# MCU.net
KiCad netlist of a schematic drawn in EAGLE
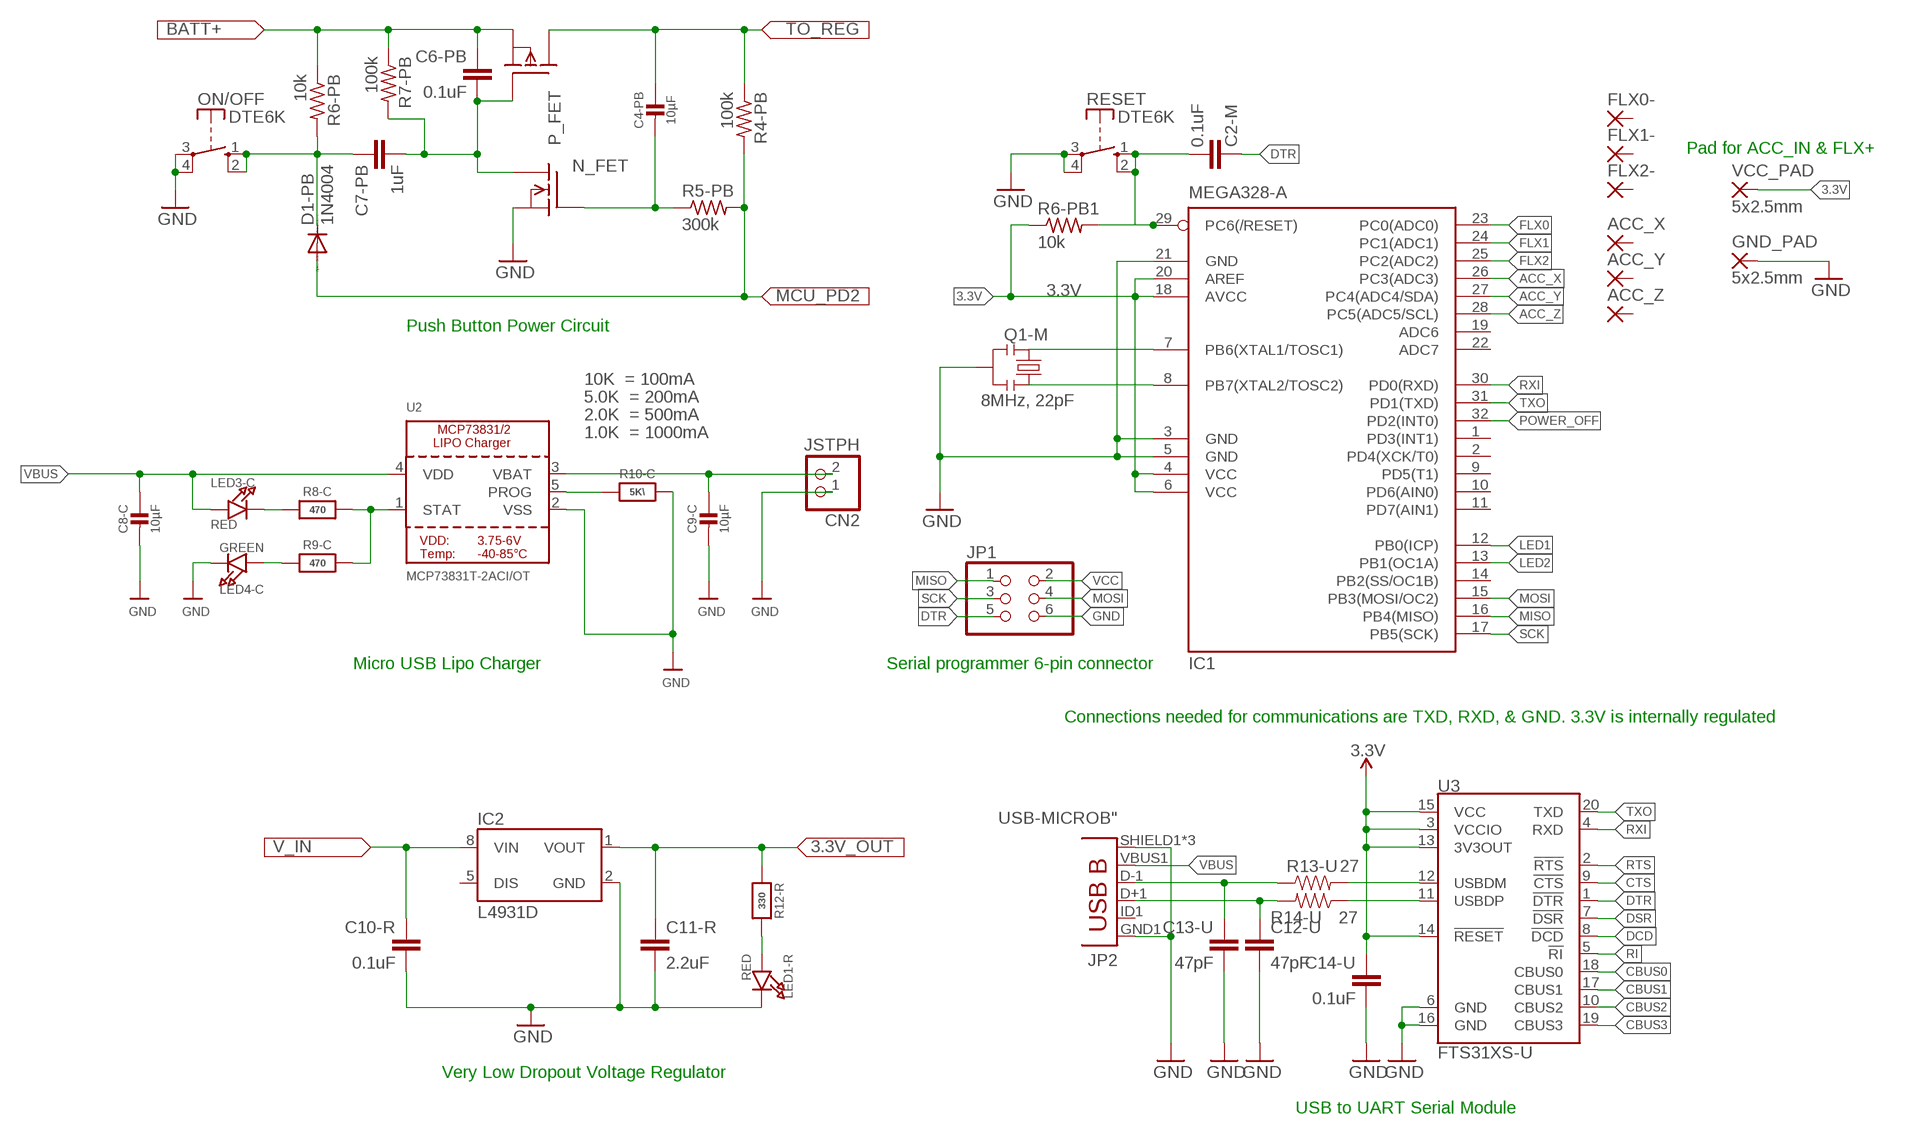
[diagram p0: schematic, sheet 1]

(export (version "E")
  (design (tool "Eeschema 10.0.6"))
  (components
    (comp (ref "ACC_X")
      (value "1,6/0,8")
      (footprint "eagle-import:1,6_0,8")
      (libsource (lib "eagle-import") (part "1,6/0,8"))
    )
    (comp (ref "ACC_Y")
      (value "1,6/0,8")
      (footprint "eagle-import:1,6_0,8")
      (libsource (lib "eagle-import") (part "1,6/0,8"))
    )
    (comp (ref "ACC_Z")
      (value "1,6/0,8")
      (footprint "eagle-import:1,6_0,8")
      (libsource (lib "eagle-import") (part "1,6/0,8"))
    )
    (comp (ref "C2-M")
      (value "0.1uF")
      (footprint "eagle-import:0603-CAP")
      (libsource (lib "eagle-import") (part "CAP0603-CAP"))
    )
    (comp (ref "C4-PB")
      (value "10µF")
      (footprint "eagle-import:0805-NO")
      (libsource (lib "eagle-import") (part "CAP_CERAMIC0805-NOOUTLINE"))
    )
    (comp (ref "C6-PB")
      (value "0.1uF")
      (footprint "eagle-import:0603-CAP")
      (libsource (lib "eagle-import") (part "0.1UF-25V(+80/-20%)(0603)"))
    )
    (comp (ref "C7-PB")
      (value "1uF")
      (footprint "eagle-import:0603-CAP")
      (libsource (lib "eagle-import") (part "0.1UF-25V(+80/-20%)(0603)"))
    )
    (comp (ref "C8-C")
      (value "10µF")
      (footprint "eagle-import:0805-NO")
      (libsource (lib "eagle-import") (part "CAP_CERAMIC0805-NOOUTLINE"))
    )
    (comp (ref "C9-C")
      (value "10µF")
      (footprint "eagle-import:0805-NO")
      (libsource (lib "eagle-import") (part "CAP_CERAMIC0805-NOOUTLINE"))
    )
    (comp (ref "C10-R")
      (value "0.1uF")
      (footprint "eagle-import:0603-CAP")
      (libsource (lib "eagle-import") (part "0.1UF-25V(+80/-20%)(0603)"))
    )
    (comp (ref "C11-R")
      (value "2.2uF")
      (footprint "eagle-import:0603-CAP")
      (libsource (lib "eagle-import") (part "0.1UF-25V(+80/-20%)(0603)"))
    )
    (comp (ref "C12-U")
      (value "47pF")
      (footprint "eagle-import:0603-CAP")
      (libsource (lib "eagle-import") (part "47PF-50V-5%(0603)"))
    )
    (comp (ref "C13-U")
      (value "47pF")
      (footprint "eagle-import:0603-CAP")
      (libsource (lib "eagle-import") (part "47PF-50V-5%(0603)"))
    )
    (comp (ref "C14-U")
      (value "0.1uF")
      (footprint "eagle-import:0603-CAP")
      (libsource (lib "eagle-import") (part "0.1UF-25V(+80/-20%)(0603)"))
    )
    (comp (ref "CN2")
      (value "JSTPH")
      (footprint "eagle-import:JSTPH2")
      (libsource (lib "eagle-import") (part "JST_2PIN"))
    )
    (comp (ref "D1-PB")
      (value "1N4004")
      (footprint "eagle-import:DO41-10")
      (libsource (lib "eagle-import") (part "1N4004"))
    )
    (comp (ref "FLX0-")
      (value "1,6/0,8")
      (footprint "eagle-import:1,6_0,8")
      (libsource (lib "eagle-import") (part "1,6/0,8"))
    )
    (comp (ref "FLX1-")
      (value "1,6/0,8")
      (footprint "eagle-import:1,6_0,8")
      (libsource (lib "eagle-import") (part "1,6/0,8"))
    )
    (comp (ref "FLX2-")
      (value "1,6/0,8")
      (footprint "eagle-import:1,6_0,8")
      (libsource (lib "eagle-import") (part "1,6/0,8"))
    )
    (comp (ref "GND_PAD")
      (value "5x2.5mm")
      (footprint "eagle-import:5-2,5")
      (libsource (lib "eagle-import") (part "WIREPADSMD5-2,5"))
    )
    (comp (ref "IC1")
      (value "MEGA328-A")
      (footprint "eagle-import:TQFP32-08")
      (fields (field (name "MPN") "ATMEGA8-16AU"))
      (libsource (lib "eagle-import") (part "MEGA8-AI"))
    )
    (comp (ref "IC2")
      (value "L4931D")
      (footprint "eagle-import:SO08")
      (libsource (lib "eagle-import") (part "L4931D"))
    )
    (comp (ref "JP1")
      (value "PINHD-2X3")
      (footprint "eagle-import:2X03")
      (libsource (lib "eagle-import") (part "PINHD-2X3"))
    )
    (comp (ref "JP2")
      (value "USB-MICROB\"")
      (footprint "eagle-import:USB-B-MICRO-SMD_V03")
      (libsource (lib "eagle-import") (part "USB-MICROB{dblquote}"))
    )
    (comp (ref "LED1-R")
      (value "RED")
      (footprint "eagle-import:CHIPLED_0805_NOOUTLINE")
      (libsource (lib "eagle-import") (part "LED0805_NOOUTLINE"))
    )
    (comp (ref "LED3-C")
      (value "RED")
      (footprint "eagle-import:CHIPLED_0805_NOOUTLINE")
      (libsource (lib "eagle-import") (part "LED0805_NOOUTLINE"))
    )
    (comp (ref "LED4-C")
      (value "GREEN")
      (footprint "eagle-import:CHIPLED_0805_NOOUTLINE")
      (libsource (lib "eagle-import") (part "LED0805_NOOUTLINE"))
    )
    (comp (ref "N_FET")
      (value "BSS101")
      (footprint "eagle-import:TO92")
      (libsource (lib "eagle-import") (part "BSS101"))
    )
    (comp (ref "ON/OFF")
      (value "DTE6K")
      (footprint "eagle-import:DTE6K")
      (libsource (lib "eagle-import") (part "DTE6K"))
    )
    (comp (ref "P_FET")
      (value "BSS92")
      (footprint "eagle-import:TO92")
      (libsource (lib "eagle-import") (part "BSS92"))
    )
    (comp (ref "Q1-M")
      (value "8MHz, 22pF")
      (footprint "eagle-import:RESONATOR-SMD-1_1")
      (libsource (lib "eagle-import") (part "RESONATOR1{colon}1"))
    )
    (comp (ref "R4-PB")
      (value "100k")
      (footprint "eagle-import:R0805")
      (libsource (lib "eagle-import") (part "R-US_R0805"))
    )
    (comp (ref "R5-PB")
      (value "300k")
      (footprint "eagle-import:R0805")
      (libsource (lib "eagle-import") (part "R-US_R0805"))
    )
    (comp (ref "R6-PB")
      (value "10k")
      (footprint "eagle-import:R0805")
      (libsource (lib "eagle-import") (part "R-US_R0805"))
    )
    (comp (ref "R6-PB1")
      (value "10k")
      (footprint "eagle-import:R0805")
      (libsource (lib "eagle-import") (part "R-US_R0805"))
    )
    (comp (ref "R7-PB")
      (value "100k")
      (footprint "eagle-import:R0805")
      (libsource (lib "eagle-import") (part "R-US_R0805"))
    )
    (comp (ref "R8-C")
      (value "470")
      (footprint "eagle-import:0805-NO")
      (libsource (lib "eagle-import") (part "RESISTOR0805_NOOUTLINE"))
    )
    (comp (ref "R9-C")
      (value "470")
      (footprint "eagle-import:0805-NO")
      (libsource (lib "eagle-import") (part "RESISTOR0805_NOOUTLINE"))
    )
    (comp (ref "R10-C")
      (value "5K\\")
      (footprint "eagle-import:0805-NO")
      (libsource (lib "eagle-import") (part "RESISTOR0805_NOOUTLINE"))
    )
    (comp (ref "R12-R")
      (value "330")
      (footprint "eagle-import:0805-NO")
      (libsource (lib "eagle-import") (part "RESISTOR0805_NOOUTLINE"))
    )
    (comp (ref "R13-U")
      (value "27")
      (footprint "eagle-import:0603-RES")
      (libsource (lib "eagle-import") (part "27OHM1/10W1%(0603)0603-RES"))
    )
    (comp (ref "R14-U")
      (value "27")
      (footprint "eagle-import:0603-RES")
      (libsource (lib "eagle-import") (part "27OHM1/10W1%(0603)0603-RES"))
    )
    (comp (ref "RESET")
      (value "DTE6K")
      (footprint "eagle-import:DTE6K")
      (libsource (lib "eagle-import") (part "DTE6K"))
    )
    (comp (ref "U2")
      (value "MCP73831T-2ACI/OT")
      (footprint "eagle-import:SOT23-5")
      (libsource (lib "eagle-import") (part "MCP73831/2"))
    )
    (comp (ref "U3")
      (value "FTS31XS-U")
      (footprint "eagle-import:SSOP20_L")
      (libsource (lib "eagle-import") (part "FT231XS"))
    )
    (comp (ref "VCC_PAD")
      (value "5x2.5mm")
      (footprint "eagle-import:5-2,5")
      (libsource (lib "eagle-import") (part "WIREPADSMD5-2,5"))
    )
  )
  (nets
    (net (code "1") (name "/VBAT") (class "Default")
      (node (ref "C6-PB") (pin "1") (pinfunction "1_1") (pintype "passive"))
      (node (ref "C9-C") (pin "1") (pinfunction "1_1") (pintype "passive"))
      (node (ref "CN2") (pin "2") (pinfunction "2_2") (pintype "passive"))
      (node (ref "P_FET") (pin "3") (pinfunction "S_3") (pintype "passive"))
      (node (ref "R6-PB") (pin "1") (pinfunction "1_1") (pintype "passive"))
      (node (ref "R7-PB") (pin "1") (pinfunction "1_1") (pintype "passive"))
      (node (ref "U2") (pin "3") (pinfunction "VBAT_3") (pintype "power_in"))
    )
    (net (code "2") (name "/V_IN") (class "Default")
      (node (ref "C10-R") (pin "1") (pinfunction "1_1") (pintype "passive"))
      (node (ref "C4-PB") (pin "1") (pinfunction "1_1") (pintype "passive"))
      (node (ref "IC2") (pin "8") (pinfunction "VIN_8") (pintype "power_in"))
      (node (ref "P_FET") (pin "2") (pinfunction "D_2") (pintype "passive"))
      (node (ref "R4-PB") (pin "1") (pinfunction "1_1") (pintype "passive"))
    )
    (net (code "3") (name "3.3V") (class "Default")
      (node (ref "C11-R") (pin "1") (pinfunction "1_1") (pintype "passive"))
      (node (ref "C14-U") (pin "1") (pinfunction "1_1") (pintype "passive"))
      (node (ref "IC1") (pin "18") (pinfunction "AVCC_18") (pintype "power_in"))
      (node (ref "IC1") (pin "20") (pinfunction "AREF_20") (pintype "passive"))
      (node (ref "IC1") (pin "4") (pinfunction "VCC_4") (pintype "power_in"))
      (node (ref "IC1") (pin "6") (pinfunction "VCC_6") (pintype "power_in"))
      (node (ref "IC2") (pin "1") (pinfunction "VOUT_1") (pintype "power_in"))
      (node (ref "R12-R") (pin "1") (pinfunction "1_1") (pintype "passive"))
      (node (ref "R6-PB1") (pin "1") (pinfunction "1_1") (pintype "passive"))
      (node (ref "U3") (pin "13") (pinfunction "3V3OUT_13") (pintype "bidirectional"))
      (node (ref "U3") (pin "14") (pinfunction "~{RESET}_14") (pintype "bidirectional"))
      (node (ref "U3") (pin "15") (pinfunction "VCC_15") (pintype "bidirectional"))
      (node (ref "U3") (pin "3") (pinfunction "VCCIO_3") (pintype "bidirectional"))
      (node (ref "VCC_PAD") (pin "1") (pinfunction "P_1") (pintype "passive"))
    )
    (net (code "4") (name "ACC_X") (class "Default")
      (node (ref "IC1") (pin "26") (pinfunction "PC3(ADC3)_26") (pintype "bidirectional"))
    )
    (net (code "5") (name "ACC_Y") (class "Default")
      (node (ref "IC1") (pin "27") (pinfunction "PC4(ADC4/SDA)_27") (pintype "bidirectional"))
    )
    (net (code "6") (name "ACC_Z") (class "Default")
      (node (ref "IC1") (pin "28") (pinfunction "PC5(ADC5/SCL)_28") (pintype "bidirectional"))
    )
    (net (code "7") (name "CBUS0") (class "Default")
      (node (ref "U3") (pin "18") (pinfunction "CBUS0_18") (pintype "bidirectional"))
    )
    (net (code "8") (name "CBUS1") (class "Default")
      (node (ref "U3") (pin "17") (pinfunction "CBUS1_17") (pintype "bidirectional"))
    )
    (net (code "9") (name "CBUS2") (class "Default")
      (node (ref "U3") (pin "10") (pinfunction "CBUS2_10") (pintype "bidirectional"))
    )
    (net (code "10") (name "CBUS3") (class "Default")
      (node (ref "U3") (pin "19") (pinfunction "CBUS3_19") (pintype "bidirectional"))
    )
    (net (code "11") (name "CTS") (class "Default")
      (node (ref "U3") (pin "9") (pinfunction "~{CTS}_9") (pintype "bidirectional"))
    )
    (net (code "12") (name "DCD") (class "Default")
      (node (ref "U3") (pin "8") (pinfunction "~{DCD}_8") (pintype "bidirectional"))
    )
    (net (code "13") (name "DSR") (class "Default")
      (node (ref "U3") (pin "7") (pinfunction "~{DSR}_7") (pintype "bidirectional"))
    )
    (net (code "14") (name "DTR") (class "Default")
      (node (ref "C2-M") (pin "2") (pinfunction "2_2") (pintype "passive"))
      (node (ref "JP1") (pin "5") (pinfunction "5_5") (pintype "passive"))
      (node (ref "U3") (pin "1") (pinfunction "~{DTR}_1") (pintype "bidirectional"))
    )
    (net (code "15") (name "FLX0") (class "Default")
      (node (ref "IC1") (pin "23") (pinfunction "PC0(ADC0)_23") (pintype "bidirectional"))
    )
    (net (code "16") (name "FLX1") (class "Default")
      (node (ref "IC1") (pin "24") (pinfunction "PC1(ADC1)_24") (pintype "bidirectional"))
    )
    (net (code "17") (name "FLX2") (class "Default")
      (node (ref "IC1") (pin "25") (pinfunction "PC2(ADC2)_25") (pintype "bidirectional"))
    )
    (net (code "18") (name "GND") (class "Default")
      (node (ref "C10-R") (pin "2") (pinfunction "2_2") (pintype "passive"))
      (node (ref "C11-R") (pin "2") (pinfunction "2_2") (pintype "passive"))
      (node (ref "C12-U") (pin "2") (pinfunction "2_2") (pintype "passive"))
      (node (ref "C13-U") (pin "2") (pinfunction "2_2") (pintype "passive"))
      (node (ref "C14-U") (pin "2") (pinfunction "2_2") (pintype "passive"))
      (node (ref "C8-C") (pin "2") (pinfunction "2_2") (pintype "passive"))
      (node (ref "C9-C") (pin "2") (pinfunction "2_2") (pintype "passive"))
      (node (ref "CN2") (pin "1") (pinfunction "1_1") (pintype "passive"))
      (node (ref "GND_PAD") (pin "1") (pinfunction "P_1") (pintype "passive"))
      (node (ref "IC1") (pin "21") (pinfunction "GND_21") (pintype "power_in"))
      (node (ref "IC1") (pin "3") (pinfunction "GND_3") (pintype "power_in"))
      (node (ref "IC1") (pin "5") (pinfunction "GND_5") (pintype "power_in"))
      (node (ref "IC2") (pin "2") (pinfunction "GND_2") (pintype "power_in"))
      (node (ref "JP1") (pin "6") (pinfunction "6_6") (pintype "passive"))
      (node (ref "JP2") (pin "GND1") (pinfunction "GND_GND1") (pintype "bidirectional"))
      (node (ref "JP2") (pin "SHIELD1") (pinfunction "SHIELD_SHIELD1") (pintype "bidirectional"))
      (node (ref "JP2") (pin "SHIELD2") (pinfunction "SHIELD_SHIELD2") (pintype "bidirectional"))
      (node (ref "JP2") (pin "SHIELD3") (pinfunction "SHIELD_SHIELD3") (pintype "bidirectional"))
      (node (ref "LED1-R") (pin "C") (pinfunction "C_C") (pintype "passive"))
      (node (ref "LED4-C") (pin "C") (pinfunction "C_C") (pintype "passive"))
      (node (ref "N_FET") (pin "1") (pinfunction "S_1") (pintype "passive"))
      (node (ref "ON/OFF") (pin "3") (pinfunction "P_3") (pintype "passive"))
      (node (ref "ON/OFF") (pin "4") (pinfunction "P_4") (pintype "passive"))
      (node (ref "Q1-M") (pin "2") (pinfunction "2_2") (pintype "passive"))
      (node (ref "R10-C") (pin "2") (pinfunction "2_2") (pintype "passive"))
      (node (ref "RESET") (pin "3") (pinfunction "P_3") (pintype "passive"))
      (node (ref "RESET") (pin "4") (pinfunction "P_4") (pintype "passive"))
      (node (ref "U2") (pin "2") (pinfunction "VSS_2") (pintype "power_in"))
      (node (ref "U3") (pin "16") (pinfunction "GND_16") (pintype "bidirectional"))
      (node (ref "U3") (pin "6") (pinfunction "GND_6") (pintype "bidirectional"))
    )
    (net (code "19") (name "LED1") (class "Default")
      (node (ref "IC1") (pin "12") (pinfunction "PB0(ICP)_12") (pintype "bidirectional"))
    )
    (net (code "20") (name "LED2") (class "Default")
      (node (ref "IC1") (pin "13") (pinfunction "PB1(OC1A)_13") (pintype "bidirectional"))
    )
    (net (code "21") (name "MISO") (class "Default")
      (node (ref "IC1") (pin "16") (pinfunction "PB4(MISO)_16") (pintype "bidirectional"))
      (node (ref "JP1") (pin "1") (pinfunction "1_1") (pintype "passive"))
    )
    (net (code "22") (name "MOSI") (class "Default")
      (node (ref "IC1") (pin "15") (pinfunction "PB3(MOSI/OC2)_15") (pintype "bidirectional"))
      (node (ref "JP1") (pin "4") (pinfunction "4_4") (pintype "passive"))
    )
    (net (code "23") (name "Net-(C7-PB-Pad1)") (class "Default")
      (node (ref "C7-PB") (pin "1") (pinfunction "1_1") (pintype "passive"))
      (node (ref "D1-PB") (pin "C") (pinfunction "C_C") (pintype "passive"))
      (node (ref "ON/OFF") (pin "1") (pinfunction "S_1") (pintype "passive"))
      (node (ref "ON/OFF") (pin "2") (pinfunction "S_2") (pintype "passive"))
      (node (ref "R6-PB") (pin "2") (pinfunction "2_2") (pintype "passive"))
    )
    (net (code "24") (name "Net-(IC1-PB6(XTAL1{slash}TOSC1))") (class "Default")
      (node (ref "IC1") (pin "7") (pinfunction "PB6(XTAL1/TOSC1)_7") (pintype "bidirectional"))
      (node (ref "Q1-M") (pin "1") (pinfunction "1_1") (pintype "passive"))
    )
    (net (code "25") (name "Net-(IC1-PB7(XTAL2{slash}TOSC2))") (class "Default")
      (node (ref "IC1") (pin "8") (pinfunction "PB7(XTAL2/TOSC2)_8") (pintype "bidirectional"))
      (node (ref "Q1-M") (pin "3") (pinfunction "3_3") (pintype "passive"))
    )
    (net (code "26") (name "Net-(IC1-PC6({slash}RESET))") (class "Default")
      (node (ref "C2-M") (pin "1") (pinfunction "1_1") (pintype "passive"))
      (node (ref "IC1") (pin "29") (pinfunction "PC6(/RESET)_29") (pintype "bidirectional"))
      (node (ref "R6-PB1") (pin "2") (pinfunction "2_2") (pintype "passive"))
      (node (ref "RESET") (pin "1") (pinfunction "S_1") (pintype "passive"))
      (node (ref "RESET") (pin "2") (pinfunction "S_2") (pintype "passive"))
    )
    (net (code "27") (name "Net-(JP2-D+)") (class "Default")
      (node (ref "C12-U") (pin "1") (pinfunction "1_1") (pintype "passive"))
      (node (ref "JP2") (pin "D+1") (pinfunction "D+_D+1") (pintype "bidirectional"))
      (node (ref "R14-U") (pin "2") (pinfunction "2_2") (pintype "passive"))
    )
    (net (code "28") (name "Net-(JP2-D-)") (class "Default")
      (node (ref "C13-U") (pin "1") (pinfunction "1_1") (pintype "passive"))
      (node (ref "JP2") (pin "D-1") (pinfunction "D-_D-1") (pintype "bidirectional"))
      (node (ref "R13-U") (pin "1") (pinfunction "1_1") (pintype "passive"))
    )
    (net (code "29") (name "Net-(LED1-R-PadA)") (class "Default")
      (node (ref "LED1-R") (pin "A") (pinfunction "A_A") (pintype "passive"))
      (node (ref "R12-R") (pin "2") (pinfunction "2_2") (pintype "passive"))
    )
    (net (code "30") (name "Net-(LED3-C-PadC)") (class "Default")
      (node (ref "LED3-C") (pin "C") (pinfunction "C_C") (pintype "passive"))
      (node (ref "R8-C") (pin "1") (pinfunction "1_1") (pintype "passive"))
    )
    (net (code "31") (name "Net-(LED4-C-PadA)") (class "Default")
      (node (ref "LED4-C") (pin "A") (pinfunction "A_A") (pintype "passive"))
      (node (ref "R9-C") (pin "1") (pinfunction "1_1") (pintype "passive"))
    )
    (net (code "32") (name "Net-(N_FET-D)") (class "Default")
      (node (ref "C6-PB") (pin "2") (pinfunction "2_2") (pintype "passive"))
      (node (ref "C7-PB") (pin "2") (pinfunction "2_2") (pintype "passive"))
      (node (ref "N_FET") (pin "3") (pinfunction "D_3") (pintype "passive"))
      (node (ref "P_FET") (pin "1") (pinfunction "G_1") (pintype "passive"))
      (node (ref "R7-PB") (pin "2") (pinfunction "2_2") (pintype "passive"))
    )
    (net (code "33") (name "Net-(N_FET-G)") (class "Default")
      (node (ref "C4-PB") (pin "2") (pinfunction "2_2") (pintype "passive"))
      (node (ref "N_FET") (pin "2") (pinfunction "G_2") (pintype "passive"))
      (node (ref "R5-PB") (pin "1") (pinfunction "1_1") (pintype "passive"))
    )
    (net (code "34") (name "Net-(U2-PROG)") (class "Default")
      (node (ref "R10-C") (pin "1") (pinfunction "1_1") (pintype "passive"))
      (node (ref "U2") (pin "5") (pinfunction "PROG_5") (pintype "input"))
    )
    (net (code "35") (name "Net-(U2-STAT)") (class "Default")
      (node (ref "R8-C") (pin "2") (pinfunction "2_2") (pintype "passive"))
      (node (ref "R9-C") (pin "2") (pinfunction "2_2") (pintype "passive"))
      (node (ref "U2") (pin "1") (pinfunction "STAT_1") (pintype "output"))
    )
    (net (code "36") (name "Net-(U3-USBDM)") (class "Default")
      (node (ref "R13-U") (pin "2") (pinfunction "2_2") (pintype "passive"))
      (node (ref "U3") (pin "12") (pinfunction "USBDM_12") (pintype "bidirectional"))
    )
    (net (code "37") (name "Net-(U3-USBDP)") (class "Default")
      (node (ref "R14-U") (pin "1") (pinfunction "1_1") (pintype "passive"))
      (node (ref "U3") (pin "11") (pinfunction "USBDP_11") (pintype "bidirectional"))
    )
    (net (code "38") (name "POWER_OFF") (class "Default")
      (node (ref "D1-PB") (pin "A") (pinfunction "A_A") (pintype "passive"))
      (node (ref "IC1") (pin "32") (pinfunction "PD2(INT0)_32") (pintype "bidirectional"))
      (node (ref "R4-PB") (pin "2") (pinfunction "2_2") (pintype "passive"))
      (node (ref "R5-PB") (pin "2") (pinfunction "2_2") (pintype "passive"))
    )
    (net (code "39") (name "RI") (class "Default")
      (node (ref "U3") (pin "5") (pinfunction "~{RI}_5") (pintype "bidirectional"))
    )
    (net (code "40") (name "RTS") (class "Default")
      (node (ref "U3") (pin "2") (pinfunction "~{RTS}_2") (pintype "bidirectional"))
    )
    (net (code "41") (name "RXI") (class "Default")
      (node (ref "IC1") (pin "30") (pinfunction "PD0(RXD)_30") (pintype "bidirectional"))
      (node (ref "U3") (pin "4") (pinfunction "RXD_4") (pintype "bidirectional"))
    )
    (net (code "42") (name "SCK") (class "Default")
      (node (ref "IC1") (pin "17") (pinfunction "PB5(SCK)_17") (pintype "bidirectional"))
      (node (ref "JP1") (pin "3") (pinfunction "3_3") (pintype "passive"))
    )
    (net (code "43") (name "TXO") (class "Default")
      (node (ref "IC1") (pin "31") (pinfunction "PD1(TXD)_31") (pintype "bidirectional"))
      (node (ref "U3") (pin "20") (pinfunction "TXD_20") (pintype "bidirectional"))
    )
    (net (code "44") (name "VBUS") (class "Default")
      (node (ref "C8-C") (pin "1") (pinfunction "1_1") (pintype "passive"))
      (node (ref "JP2") (pin "VBUS1") (pinfunction "VBUS_VBUS1") (pintype "bidirectional"))
      (node (ref "LED3-C") (pin "A") (pinfunction "A_A") (pintype "passive"))
      (node (ref "U2") (pin "4") (pinfunction "VDD_4") (pintype "power_in"))
    )
    (net (code "45") (name "VCC") (class "Default")
      (node (ref "JP1") (pin "2") (pinfunction "2_2") (pintype "passive"))
    )
    (net (code "46") (name "unconnected-(ACC_X-P-Pad1)") (class "Default")
      (node (ref "ACC_X") (pin "1") (pinfunction "P_1") (pintype "passive"))
    )
    (net (code "47") (name "unconnected-(ACC_Y-P-Pad1)") (class "Default")
      (node (ref "ACC_Y") (pin "1") (pinfunction "P_1") (pintype "passive"))
    )
    (net (code "48") (name "unconnected-(ACC_Z-P-Pad1)") (class "Default")
      (node (ref "ACC_Z") (pin "1") (pinfunction "P_1") (pintype "passive"))
    )
    (net (code "49") (name "unconnected-(FLX0--P-Pad1)") (class "Default")
      (node (ref "FLX0-") (pin "1") (pinfunction "P_1") (pintype "passive"))
    )
    (net (code "50") (name "unconnected-(FLX1--P-Pad1)") (class "Default")
      (node (ref "FLX1-") (pin "1") (pinfunction "P_1") (pintype "passive"))
    )
    (net (code "51") (name "unconnected-(FLX2--P-Pad1)") (class "Default")
      (node (ref "FLX2-") (pin "1") (pinfunction "P_1") (pintype "passive"))
    )
    (net (code "52") (name "unconnected-(IC1-ADC6-Pad19)") (class "Default")
      (node (ref "IC1") (pin "19") (pinfunction "ADC6_19") (pintype "bidirectional"))
    )
    (net (code "53") (name "unconnected-(IC1-ADC7-Pad22)") (class "Default")
      (node (ref "IC1") (pin "22") (pinfunction "ADC7_22") (pintype "bidirectional"))
    )
    (net (code "54") (name "unconnected-(IC1-PB2(SS{slash}OC1B)-Pad14)") (class "Default")
      (node (ref "IC1") (pin "14") (pinfunction "PB2(SS/OC1B)_14") (pintype "bidirectional"))
    )
    (net (code "55") (name "unconnected-(IC1-PD3(INT1)-Pad1)") (class "Default")
      (node (ref "IC1") (pin "1") (pinfunction "PD3(INT1)_1") (pintype "bidirectional"))
    )
    (net (code "56") (name "unconnected-(IC1-PD4(XCK{slash}T0)-Pad2)") (class "Default")
      (node (ref "IC1") (pin "2") (pinfunction "PD4(XCK/T0)_2") (pintype "bidirectional"))
    )
    (net (code "57") (name "unconnected-(IC1-PD5(T1)-Pad9)") (class "Default")
      (node (ref "IC1") (pin "9") (pinfunction "PD5(T1)_9") (pintype "bidirectional"))
    )
    (net (code "58") (name "unconnected-(IC1-PD6(AIN0)-Pad10)") (class "Default")
      (node (ref "IC1") (pin "10") (pinfunction "PD6(AIN0)_10") (pintype "bidirectional"))
    )
    (net (code "59") (name "unconnected-(IC1-PD7(AIN1)-Pad11)") (class "Default")
      (node (ref "IC1") (pin "11") (pinfunction "PD7(AIN1)_11") (pintype "bidirectional"))
    )
    (net (code "60") (name "unconnected-(IC2-DIS-Pad5)") (class "Default")
      (node (ref "IC2") (pin "5") (pinfunction "DIS_5") (pintype "passive"))
    )
    (net (code "61") (name "unconnected-(JP2-USBID-PadID1)") (class "Default")
      (node (ref "JP2") (pin "ID1") (pinfunction "USBID_ID1") (pintype "bidirectional"))
    )
  )
)
